# FPGA_board-v1.net
KiCad netlist of a schematic drawn in EAGLE
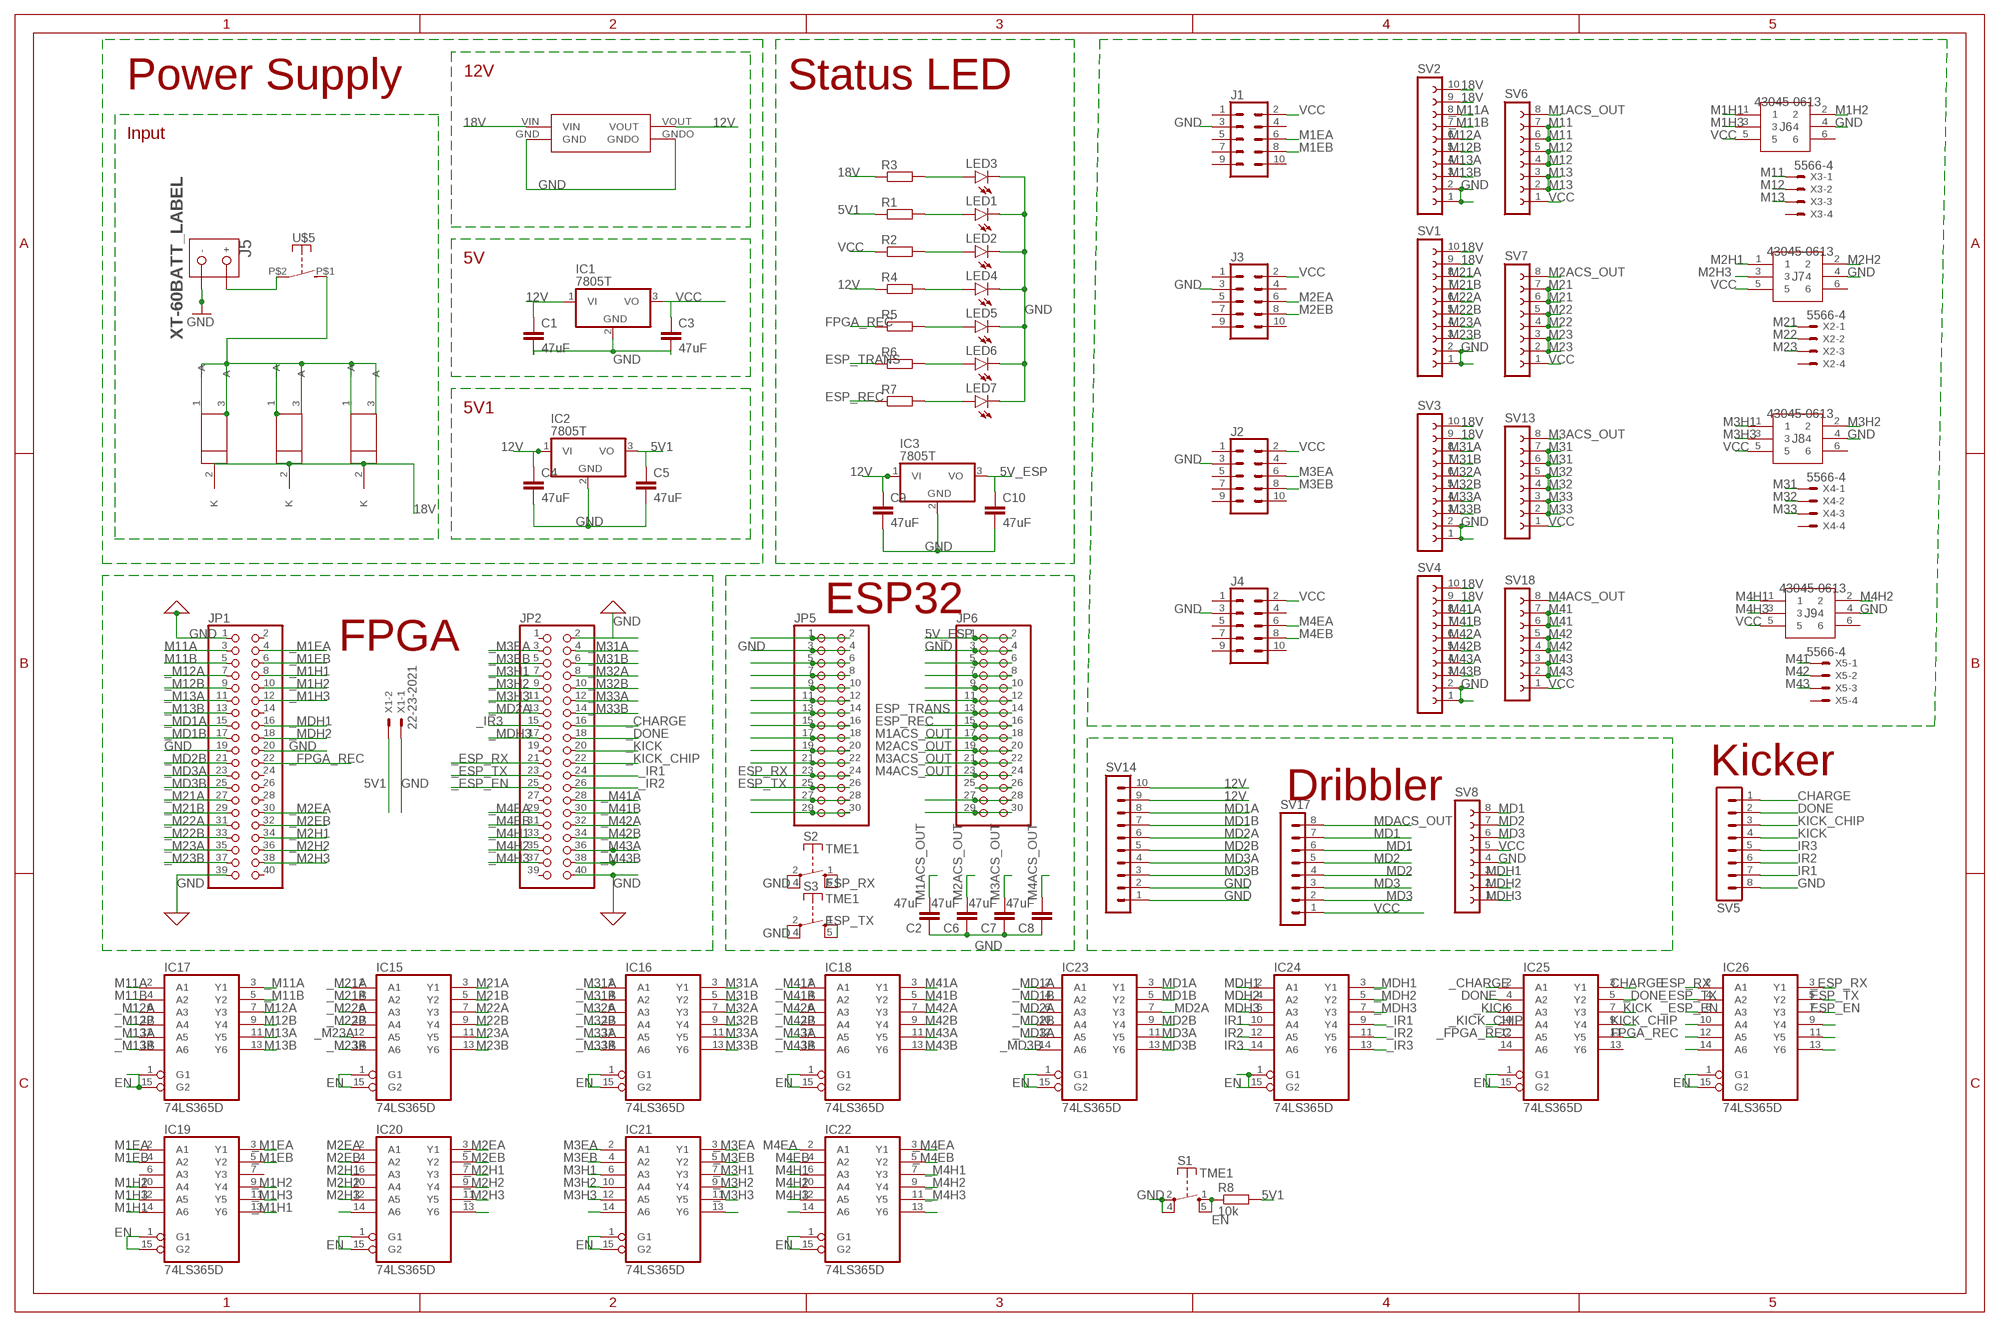
[diagram p0: schematic, sheet 1]

(export (version "E")
  (design (tool "Eeschema 10.0.6"))
  (components
    (comp (ref "C1")
      (value "47uF")
      (footprint "eagle-import:C1206")
      (libsource (lib "eagle-import") (part "C-EUC1206"))
    )
    (comp (ref "C2")
      (value "47uF")
      (footprint "eagle-import:C1206")
      (libsource (lib "eagle-import") (part "C-EUC1206"))
    )
    (comp (ref "C3")
      (value "47uF")
      (footprint "eagle-import:C1206")
      (libsource (lib "eagle-import") (part "C-EUC1206"))
    )
    (comp (ref "C4")
      (value "47uF")
      (footprint "eagle-import:C1206")
      (libsource (lib "eagle-import") (part "C-EUC1206"))
    )
    (comp (ref "C5")
      (value "47uF")
      (footprint "eagle-import:C1206")
      (libsource (lib "eagle-import") (part "C-EUC1206"))
    )
    (comp (ref "C6")
      (value "47uF")
      (footprint "eagle-import:C1206")
      (libsource (lib "eagle-import") (part "C-EUC1206"))
    )
    (comp (ref "C7")
      (value "47uF")
      (footprint "eagle-import:C1206")
      (libsource (lib "eagle-import") (part "C-EUC1206"))
    )
    (comp (ref "C8")
      (value "47uF")
      (footprint "eagle-import:C1206")
      (libsource (lib "eagle-import") (part "C-EUC1206"))
    )
    (comp (ref "C9")
      (value "47uF")
      (footprint "eagle-import:C1206")
      (libsource (lib "eagle-import") (part "C-EUC1206"))
    )
    (comp (ref "C10")
      (value "47uF")
      (footprint "eagle-import:C1206")
      (libsource (lib "eagle-import") (part "C-EUC1206"))
    )
    (comp (ref "IC1")
      (value "7805T")
      (footprint "eagle-import:TO220H")
      (libsource (lib "eagle-import") (part "78T05"))
    )
    (comp (ref "IC2")
      (value "7805T")
      (footprint "eagle-import:TO220H")
      (libsource (lib "eagle-import") (part "78T05"))
    )
    (comp (ref "IC3")
      (value "7805T")
      (footprint "eagle-import:TO220H")
      (libsource (lib "eagle-import") (part "78T05"))
    )
    (comp (ref "IC15")
      (value "74LS365D")
      (footprint "eagle-import:SO16")
      (libsource (lib "eagle-import") (part "74365DLS"))
    )
    (comp (ref "IC16")
      (value "74LS365D")
      (footprint "eagle-import:SO16")
      (libsource (lib "eagle-import") (part "74365DLS"))
    )
    (comp (ref "IC17")
      (value "74LS365D")
      (footprint "eagle-import:SO16")
      (libsource (lib "eagle-import") (part "74365DLS"))
    )
    (comp (ref "IC18")
      (value "74LS365D")
      (footprint "eagle-import:SO16")
      (libsource (lib "eagle-import") (part "74365DLS"))
    )
    (comp (ref "IC19")
      (value "74LS365D")
      (footprint "eagle-import:SO16")
      (libsource (lib "eagle-import") (part "74365DLS"))
    )
    (comp (ref "IC20")
      (value "74LS365D")
      (footprint "eagle-import:SO16")
      (libsource (lib "eagle-import") (part "74365DLS"))
    )
    (comp (ref "IC21")
      (value "74LS365D")
      (footprint "eagle-import:SO16")
      (libsource (lib "eagle-import") (part "74365DLS"))
    )
    (comp (ref "IC22")
      (value "74LS365D")
      (footprint "eagle-import:SO16")
      (libsource (lib "eagle-import") (part "74365DLS"))
    )
    (comp (ref "IC23")
      (value "74LS365D")
      (footprint "eagle-import:SO16")
      (libsource (lib "eagle-import") (part "74365DLS"))
    )
    (comp (ref "IC24")
      (value "74LS365D")
      (footprint "eagle-import:SO16")
      (libsource (lib "eagle-import") (part "74365DLS"))
    )
    (comp (ref "IC25")
      (value "74LS365D")
      (footprint "eagle-import:SO16")
      (libsource (lib "eagle-import") (part "74365DLS"))
    )
    (comp (ref "IC26")
      (value "74LS365D")
      (footprint "eagle-import:SO16")
      (libsource (lib "eagle-import") (part "74365DLS"))
    )
    (comp (ref "J1")
      (value "CONN_05X2SHD_LOCK")
      (footprint "eagle-import:2X5-SHROUDED_LOCK")
      (libsource (lib "eagle-import") (part "CONN_05X2SHD_LOCK"))
    )
    (comp (ref "J2")
      (value "CONN_05X2SHD_LOCK")
      (footprint "eagle-import:2X5-SHROUDED_LOCK")
      (libsource (lib "eagle-import") (part "CONN_05X2SHD_LOCK"))
    )
    (comp (ref "J3")
      (value "CONN_05X2SHD_LOCK")
      (footprint "eagle-import:2X5-SHROUDED_LOCK")
      (libsource (lib "eagle-import") (part "CONN_05X2SHD_LOCK"))
    )
    (comp (ref "J4")
      (value "CONN_05X2SHD_LOCK")
      (footprint "eagle-import:2X5-SHROUDED_LOCK")
      (libsource (lib "eagle-import") (part "CONN_05X2SHD_LOCK"))
    )
    (comp (ref "J5")
      (value "XT-60BATT_LABEL")
      (footprint "eagle-import:XT-60")
      (libsource (lib "eagle-import") (part "XT-60BATT_LABEL"))
    )
    (comp (ref "J6")
      (value "43045-0613")
      (footprint "eagle-import:43045-0613")
      (fields (field (name "MOUSER_PART_NUMBER") "538-43045-0613") (field (name "RS_PART_NUMBER") "6700377P"))
      (libsource (lib "eagle-import") (part "43045-0613"))
    )
    (comp (ref "J7")
      (value "43045-0613")
      (footprint "eagle-import:43045-0613")
      (fields (field (name "MOUSER_PART_NUMBER") "538-43045-0613") (field (name "RS_PART_NUMBER") "6700377P"))
      (libsource (lib "eagle-import") (part "43045-0613"))
    )
    (comp (ref "J8")
      (value "43045-0613")
      (footprint "eagle-import:43045-0613")
      (fields (field (name "MOUSER_PART_NUMBER") "538-43045-0613") (field (name "RS_PART_NUMBER") "6700377P"))
      (libsource (lib "eagle-import") (part "43045-0613"))
    )
    (comp (ref "J9")
      (value "43045-0613")
      (footprint "eagle-import:43045-0613")
      (fields (field (name "MOUSER_PART_NUMBER") "538-43045-0613") (field (name "RS_PART_NUMBER") "6700377P"))
      (libsource (lib "eagle-import") (part "43045-0613"))
    )
    (comp (ref "JP1")
      (value "PINHD-2X20")
      (footprint "eagle-import:2X20")
      (libsource (lib "eagle-import") (part "PINHD-2X20"))
    )
    (comp (ref "JP2")
      (value "PINHD-2X20")
      (footprint "eagle-import:2X20")
      (libsource (lib "eagle-import") (part "PINHD-2X20"))
    )
    (comp (ref "JP5")
      (value "PINHD-2X15")
      (footprint "eagle-import:2X15")
      (libsource (lib "eagle-import") (part "PINHD-2X15"))
    )
    (comp (ref "JP6")
      (value "PINHD-2X15")
      (footprint "eagle-import:2X15")
      (libsource (lib "eagle-import") (part "PINHD-2X15"))
    )
    (comp (ref "LED1")
      (value "LEDSMT1206")
      (footprint "eagle-import:1206")
      (libsource (lib "eagle-import") (part "LEDSMT1206"))
    )
    (comp (ref "LED2")
      (value "LEDSMT1206")
      (footprint "eagle-import:1206")
      (libsource (lib "eagle-import") (part "LEDSMT1206"))
    )
    (comp (ref "LED3")
      (value "LEDSMT1206")
      (footprint "eagle-import:1206")
      (libsource (lib "eagle-import") (part "LEDSMT1206"))
    )
    (comp (ref "LED4")
      (value "LEDSMT1206")
      (footprint "eagle-import:1206")
      (libsource (lib "eagle-import") (part "LEDSMT1206"))
    )
    (comp (ref "LED5")
      (value "LEDSMT1206")
      (footprint "eagle-import:1206")
      (libsource (lib "eagle-import") (part "LEDSMT1206"))
    )
    (comp (ref "LED6")
      (value "LEDSMT1206")
      (footprint "eagle-import:1206")
      (libsource (lib "eagle-import") (part "LEDSMT1206"))
    )
    (comp (ref "LED7")
      (value "LEDSMT1206")
      (footprint "eagle-import:1206")
      (libsource (lib "eagle-import") (part "LEDSMT1206"))
    )
    (comp (ref "R1")
      (value "R-EU_R1206")
      (footprint "eagle-import:R1206")
      (libsource (lib "eagle-import") (part "R-EU_R1206"))
    )
    (comp (ref "R2")
      (value "R-EU_R1206")
      (footprint "eagle-import:R1206")
      (libsource (lib "eagle-import") (part "R-EU_R1206"))
    )
    (comp (ref "R3")
      (value "R-EU_R1206")
      (footprint "eagle-import:R1206")
      (libsource (lib "eagle-import") (part "R-EU_R1206"))
    )
    (comp (ref "R4")
      (value "R-EU_R1206")
      (footprint "eagle-import:R1206")
      (libsource (lib "eagle-import") (part "R-EU_R1206"))
    )
    (comp (ref "R5")
      (value "R-EU_R1206")
      (footprint "eagle-import:R1206")
      (libsource (lib "eagle-import") (part "R-EU_R1206"))
    )
    (comp (ref "R6")
      (value "R-EU_R1206")
      (footprint "eagle-import:R1206")
      (libsource (lib "eagle-import") (part "R-EU_R1206"))
    )
    (comp (ref "R7")
      (value "R-EU_R1206")
      (footprint "eagle-import:R1206")
      (libsource (lib "eagle-import") (part "R-EU_R1206"))
    )
    (comp (ref "R8")
      (value "10k")
      (footprint "eagle-import:0204_7")
      (libsource (lib "eagle-import") (part "R-EU_0204/7"))
    )
    (comp (ref "S1")
      (value "TME1")
      (footprint "eagle-import:TME1")
      (libsource (lib "eagle-import") (part "TME1"))
    )
    (comp (ref "S2")
      (value "TME1")
      (footprint "eagle-import:TME1")
      (libsource (lib "eagle-import") (part "TME1"))
    )
    (comp (ref "S3")
      (value "TME1")
      (footprint "eagle-import:TME1")
      (libsource (lib "eagle-import") (part "TME1"))
    )
    (comp (ref "SV1")
      (value "FE10-1")
      (footprint "eagle-import:FE10")
      (libsource (lib "eagle-import") (part "FE10-1"))
    )
    (comp (ref "SV2")
      (value "FE10-1")
      (footprint "eagle-import:FE10")
      (libsource (lib "eagle-import") (part "FE10-1"))
    )
    (comp (ref "SV3")
      (value "FE10-1")
      (footprint "eagle-import:FE10")
      (libsource (lib "eagle-import") (part "FE10-1"))
    )
    (comp (ref "SV4")
      (value "FE10-1")
      (footprint "eagle-import:FE10")
      (libsource (lib "eagle-import") (part "FE10-1"))
    )
    (comp (ref "SV5")
      (value "MA08-1")
      (footprint "eagle-import:MA08-1")
      (libsource (lib "eagle-import") (part "MA08-1"))
    )
    (comp (ref "SV6")
      (value "FE08-1")
      (footprint "eagle-import:FE08")
      (libsource (lib "eagle-import") (part "FE08-1"))
    )
    (comp (ref "SV7")
      (value "FE08-1")
      (footprint "eagle-import:FE08")
      (libsource (lib "eagle-import") (part "FE08-1"))
    )
    (comp (ref "SV8")
      (value "FE08-1")
      (footprint "eagle-import:FE08")
      (libsource (lib "eagle-import") (part "FE08-1"))
    )
    (comp (ref "SV13")
      (value "FE08-1")
      (footprint "eagle-import:FE08")
      (libsource (lib "eagle-import") (part "FE08-1"))
    )
    (comp (ref "SV14")
      (value "MA10-1")
      (footprint "eagle-import:MA10-1")
      (libsource (lib "eagle-import") (part "MA10-1"))
    )
    (comp (ref "SV17")
      (value "MA08-1")
      (footprint "eagle-import:MA08-1")
      (libsource (lib "eagle-import") (part "MA08-1"))
    )
    (comp (ref "SV18")
      (value "FE08-1")
      (footprint "eagle-import:FE08")
      (libsource (lib "eagle-import") (part "FE08-1"))
    )
    (comp (ref "U$4")
      (value "BUCK")
      (footprint "eagle-import:BUCK")
      (libsource (lib "eagle-import") (part "BUCK"))
    )
    (comp (ref "U$5")
      (value "SWITCH_DA10")
      (footprint "eagle-import:DA10")
      (libsource (lib "eagle-import") (part "SWITCH_DA10"))
    )
    (comp (ref "U1")
      (value "LP38690DT-3.3")
      (footprint "eagle-import:TO228P1042X238-3N")
      (libsource (lib "eagle-import") (part "LP38690DT-3.3"))
    )
    (comp (ref "U2")
      (value "LP38690DT-3.3")
      (footprint "eagle-import:TO228P1042X238-3N")
      (libsource (lib "eagle-import") (part "LP38690DT-3.3"))
    )
    (comp (ref "U3")
      (value "LP38690DT-3.3")
      (footprint "eagle-import:TO228P1042X238-3N")
      (libsource (lib "eagle-import") (part "LP38690DT-3.3"))
    )
    (comp (ref "X1")
      (value "22-23-2021")
      (footprint "eagle-import:22-23-2021")
      (fields (field (name "MF") "MOLEX"))
      (libsource (lib "eagle-import") (part "22-23-2021"))
    )
    (comp (ref "X2")
      (value "5566-4")
      (footprint "eagle-import:5566-4")
      (fields (field (name "MF") "MOLEX"))
      (libsource (lib "eagle-import") (part "5566-4"))
    )
    (comp (ref "X3")
      (value "5566-4")
      (footprint "eagle-import:5566-4")
      (fields (field (name "MF") "MOLEX"))
      (libsource (lib "eagle-import") (part "5566-4"))
    )
    (comp (ref "X4")
      (value "5566-4")
      (footprint "eagle-import:5566-4")
      (fields (field (name "MF") "MOLEX"))
      (libsource (lib "eagle-import") (part "5566-4"))
    )
    (comp (ref "X5")
      (value "5566-4")
      (footprint "eagle-import:5566-4")
      (fields (field (name "MF") "MOLEX"))
      (libsource (lib "eagle-import") (part "5566-4"))
    )
  )
  (nets
    (net (code "1") (name "/5V1") (class "Default")
      (node (ref "C5") (pin "1") (pinfunction "1_1") (pintype "passive"))
      (node (ref "IC2") (pin "3") (pinfunction "VO_3") (pintype "passive"))
      (node (ref "R1") (pin "1") (pinfunction "1_1") (pintype "passive"))
      (node (ref "R8") (pin "2") (pinfunction "2_2") (pintype "passive"))
      (node (ref "X1") (pin "2") (pinfunction "S_2") (pintype "passive"))
    )
    (net (code "2") (name "/5V_ESP") (class "Default")
      (node (ref "C10") (pin "1") (pinfunction "1_1") (pintype "passive"))
      (node (ref "IC3") (pin "3") (pinfunction "VO_3") (pintype "passive"))
      (node (ref "JP6") (pin "1") (pinfunction "1_1") (pintype "passive"))
      (node (ref "JP6") (pin "2") (pinfunction "2_2") (pintype "passive"))
    )
    (net (code "3") (name "/12V") (class "Default")
      (node (ref "C1") (pin "1") (pinfunction "1_1") (pintype "passive"))
      (node (ref "C4") (pin "1") (pinfunction "1_1") (pintype "passive"))
      (node (ref "C9") (pin "1") (pinfunction "1_1") (pintype "passive"))
      (node (ref "IC1") (pin "1") (pinfunction "VI_1") (pintype "input"))
      (node (ref "IC2") (pin "1") (pinfunction "VI_1") (pintype "input"))
      (node (ref "IC3") (pin "1") (pinfunction "VI_1") (pintype "input"))
      (node (ref "R4") (pin "1") (pinfunction "1_1") (pintype "passive"))
      (node (ref "SV14") (pin "10") (pinfunction "10_10") (pintype "passive"))
      (node (ref "SV14") (pin "9") (pinfunction "9_9") (pintype "passive"))
      (node (ref "U$4") (pin "VOUT") (pinfunction "VOUT_VOUT") (pintype "bidirectional"))
    )
    (net (code "4") (name "/18V") (class "Default")
      (node (ref "R3") (pin "1") (pinfunction "1_1") (pintype "passive"))
      (node (ref "SV1") (pin "10") (pinfunction "10_10") (pintype "passive"))
      (node (ref "SV1") (pin "9") (pinfunction "9_9") (pintype "passive"))
      (node (ref "SV2") (pin "10") (pinfunction "10_10") (pintype "passive"))
      (node (ref "SV2") (pin "9") (pinfunction "9_9") (pintype "passive"))
      (node (ref "SV3") (pin "10") (pinfunction "10_10") (pintype "passive"))
      (node (ref "SV3") (pin "9") (pinfunction "9_9") (pintype "passive"))
      (node (ref "SV4") (pin "10") (pinfunction "10_10") (pintype "passive"))
      (node (ref "SV4") (pin "9") (pinfunction "9_9") (pintype "passive"))
      (node (ref "U$4") (pin "VIN") (pinfunction "VIN_VIN") (pintype "bidirectional"))
      (node (ref "U1") (pin "2") (pinfunction "K_2") (pintype "bidirectional"))
      (node (ref "U2") (pin "2") (pinfunction "K_2") (pintype "bidirectional"))
      (node (ref "U3") (pin "2") (pinfunction "K_2") (pintype "bidirectional"))
    )
    (net (code "5") (name "/CHARGE") (class "Default")
      (node (ref "IC25") (pin "3") (pinfunction "Y1_3") (pintype "tri_state"))
      (node (ref "SV5") (pin "1") (pinfunction "1_1") (pintype "passive"))
    )
    (net (code "6") (name "/DONE") (class "Default")
      (node (ref "IC25") (pin "4") (pinfunction "A2_4") (pintype "input"))
      (node (ref "SV5") (pin "2") (pinfunction "2_2") (pintype "passive"))
    )
    (net (code "7") (name "/EN") (class "Default")
      (node (ref "IC15") (pin "1") (pinfunction "G1_1") (pintype "input"))
      (node (ref "IC15") (pin "15") (pinfunction "G2_15") (pintype "input"))
      (node (ref "IC16") (pin "1") (pinfunction "G1_1") (pintype "input"))
      (node (ref "IC16") (pin "15") (pinfunction "G2_15") (pintype "input"))
      (node (ref "IC17") (pin "1") (pinfunction "G1_1") (pintype "input"))
      (node (ref "IC17") (pin "15") (pinfunction "G2_15") (pintype "input"))
      (node (ref "IC18") (pin "1") (pinfunction "G1_1") (pintype "input"))
      (node (ref "IC18") (pin "15") (pinfunction "G2_15") (pintype "input"))
      (node (ref "IC19") (pin "1") (pinfunction "G1_1") (pintype "input"))
      (node (ref "IC19") (pin "15") (pinfunction "G2_15") (pintype "input"))
      (node (ref "IC20") (pin "1") (pinfunction "G1_1") (pintype "input"))
      (node (ref "IC20") (pin "15") (pinfunction "G2_15") (pintype "input"))
      (node (ref "IC21") (pin "1") (pinfunction "G1_1") (pintype "input"))
      (node (ref "IC21") (pin "15") (pinfunction "G2_15") (pintype "input"))
      (node (ref "IC22") (pin "1") (pinfunction "G1_1") (pintype "input"))
      (node (ref "IC22") (pin "15") (pinfunction "G2_15") (pintype "input"))
      (node (ref "IC23") (pin "1") (pinfunction "G1_1") (pintype "input"))
      (node (ref "IC23") (pin "15") (pinfunction "G2_15") (pintype "input"))
      (node (ref "IC24") (pin "1") (pinfunction "G1_1") (pintype "input"))
      (node (ref "IC24") (pin "15") (pinfunction "G2_15") (pintype "input"))
      (node (ref "IC25") (pin "1") (pinfunction "G1_1") (pintype "input"))
      (node (ref "IC25") (pin "15") (pinfunction "G2_15") (pintype "input"))
      (node (ref "IC26") (pin "1") (pinfunction "G1_1") (pintype "input"))
      (node (ref "IC26") (pin "15") (pinfunction "G2_15") (pintype "input"))
      (node (ref "R8") (pin "1") (pinfunction "1_1") (pintype "passive"))
      (node (ref "S1") (pin "1") (pinfunction "S_1") (pintype "passive"))
      (node (ref "S1") (pin "5") (pinfunction "S_5") (pintype "passive"))
    )
    (net (code "8") (name "/ESP_EN") (class "Default")
      (node (ref "IC26") (pin "7") (pinfunction "Y3_7") (pintype "tri_state"))
    )
    (net (code "9") (name "/ESP_REC") (class "Default")
      (node (ref "JP6") (pin "15") (pinfunction "15_15") (pintype "passive"))
      (node (ref "JP6") (pin "16") (pinfunction "16_16") (pintype "passive"))
      (node (ref "R7") (pin "1") (pinfunction "1_1") (pintype "passive"))
    )
    (net (code "10") (name "/ESP_RX") (class "Default")
      (node (ref "IC26") (pin "2") (pinfunction "A1_2") (pintype "input"))
      (node (ref "JP5") (pin "23") (pinfunction "23_23") (pintype "passive"))
      (node (ref "JP5") (pin "24") (pinfunction "24_24") (pintype "passive"))
      (node (ref "S2") (pin "1") (pinfunction "S_1") (pintype "passive"))
      (node (ref "S2") (pin "5") (pinfunction "S_5") (pintype "passive"))
    )
    (net (code "11") (name "/ESP_TRANS") (class "Default")
      (node (ref "JP6") (pin "13") (pinfunction "13_13") (pintype "passive"))
      (node (ref "JP6") (pin "14") (pinfunction "14_14") (pintype "passive"))
      (node (ref "R6") (pin "1") (pinfunction "1_1") (pintype "passive"))
    )
    (net (code "12") (name "/ESP_TX") (class "Default")
      (node (ref "IC26") (pin "5") (pinfunction "Y2_5") (pintype "tri_state"))
      (node (ref "JP5") (pin "25") (pinfunction "25_25") (pintype "passive"))
      (node (ref "JP5") (pin "26") (pinfunction "26_26") (pintype "passive"))
      (node (ref "S3") (pin "1") (pinfunction "S_1") (pintype "passive"))
      (node (ref "S3") (pin "5") (pinfunction "S_5") (pintype "passive"))
    )
    (net (code "13") (name "/FPGA_REC") (class "Default")
      (node (ref "IC25") (pin "11") (pinfunction "Y5_11") (pintype "tri_state"))
      (node (ref "R5") (pin "1") (pinfunction "1_1") (pintype "passive"))
    )
    (net (code "14") (name "/IR1") (class "Default")
      (node (ref "IC24") (pin "10") (pinfunction "A4_10") (pintype "input"))
      (node (ref "SV5") (pin "7") (pinfunction "7_7") (pintype "passive"))
    )
    (net (code "15") (name "/IR2") (class "Default")
      (node (ref "IC24") (pin "12") (pinfunction "A5_12") (pintype "input"))
      (node (ref "SV5") (pin "6") (pinfunction "6_6") (pintype "passive"))
    )
    (net (code "16") (name "/IR3") (class "Default")
      (node (ref "IC24") (pin "14") (pinfunction "A6_14") (pintype "input"))
      (node (ref "SV5") (pin "5") (pinfunction "5_5") (pintype "passive"))
    )
    (net (code "17") (name "/KICK") (class "Default")
      (node (ref "IC25") (pin "7") (pinfunction "Y3_7") (pintype "tri_state"))
      (node (ref "SV5") (pin "4") (pinfunction "4_4") (pintype "passive"))
    )
    (net (code "18") (name "/KICK_CHIP") (class "Default")
      (node (ref "IC25") (pin "9") (pinfunction "Y4_9") (pintype "tri_state"))
      (node (ref "SV5") (pin "3") (pinfunction "3_3") (pintype "passive"))
    )
    (net (code "19") (name "/M1ACS_OUT") (class "Default")
      (node (ref "C2") (pin "2") (pinfunction "2_2") (pintype "passive"))
      (node (ref "JP6") (pin "17") (pinfunction "17_17") (pintype "passive"))
      (node (ref "JP6") (pin "18") (pinfunction "18_18") (pintype "passive"))
      (node (ref "SV6") (pin "8") (pinfunction "8_8") (pintype "passive"))
    )
    (net (code "20") (name "/M1EA") (class "Default")
      (node (ref "IC19") (pin "2") (pinfunction "A1_2") (pintype "input"))
      (node (ref "J1") (pin "6") (pinfunction "6_6") (pintype "passive"))
    )
    (net (code "21") (name "/M1EB") (class "Default")
      (node (ref "IC19") (pin "4") (pinfunction "A2_4") (pintype "input"))
      (node (ref "J1") (pin "8") (pinfunction "8_8") (pintype "passive"))
    )
    (net (code "22") (name "/M1H1") (class "Default")
      (node (ref "IC19") (pin "14") (pinfunction "A6_14") (pintype "input"))
      (node (ref "J6") (pin "1") (pinfunction "1_1") (pintype "bidirectional"))
    )
    (net (code "23") (name "/M1H2") (class "Default")
      (node (ref "IC19") (pin "10") (pinfunction "A4_10") (pintype "input"))
      (node (ref "J6") (pin "2") (pinfunction "2_2") (pintype "bidirectional"))
    )
    (net (code "24") (name "/M1H3") (class "Default")
      (node (ref "IC19") (pin "12") (pinfunction "A5_12") (pintype "input"))
      (node (ref "J6") (pin "3") (pinfunction "3_3") (pintype "bidirectional"))
    )
    (net (code "25") (name "/M2ACS_OUT") (class "Default")
      (node (ref "C6") (pin "2") (pinfunction "2_2") (pintype "passive"))
      (node (ref "JP6") (pin "19") (pinfunction "19_19") (pintype "passive"))
      (node (ref "JP6") (pin "20") (pinfunction "20_20") (pintype "passive"))
      (node (ref "SV7") (pin "8") (pinfunction "8_8") (pintype "passive"))
    )
    (net (code "26") (name "/M2EA") (class "Default")
      (node (ref "IC20") (pin "2") (pinfunction "A1_2") (pintype "input"))
      (node (ref "J3") (pin "6") (pinfunction "6_6") (pintype "passive"))
    )
    (net (code "27") (name "/M2EB") (class "Default")
      (node (ref "IC20") (pin "4") (pinfunction "A2_4") (pintype "input"))
      (node (ref "J3") (pin "8") (pinfunction "8_8") (pintype "passive"))
    )
    (net (code "28") (name "/M2H1") (class "Default")
      (node (ref "IC20") (pin "6") (pinfunction "A3_6") (pintype "input"))
      (node (ref "J7") (pin "1") (pinfunction "1_1") (pintype "bidirectional"))
    )
    (net (code "29") (name "/M2H2") (class "Default")
      (node (ref "IC20") (pin "10") (pinfunction "A4_10") (pintype "input"))
      (node (ref "J7") (pin "2") (pinfunction "2_2") (pintype "bidirectional"))
    )
    (net (code "30") (name "/M2H3") (class "Default")
      (node (ref "IC20") (pin "12") (pinfunction "A5_12") (pintype "input"))
      (node (ref "J7") (pin "3") (pinfunction "3_3") (pintype "bidirectional"))
    )
    (net (code "31") (name "/M3ACS_OUT") (class "Default")
      (node (ref "C7") (pin "2") (pinfunction "2_2") (pintype "passive"))
      (node (ref "JP6") (pin "21") (pinfunction "21_21") (pintype "passive"))
      (node (ref "JP6") (pin "22") (pinfunction "22_22") (pintype "passive"))
      (node (ref "SV13") (pin "8") (pinfunction "8_8") (pintype "passive"))
    )
    (net (code "32") (name "/M3EA") (class "Default")
      (node (ref "IC21") (pin "2") (pinfunction "A1_2") (pintype "input"))
      (node (ref "J2") (pin "6") (pinfunction "6_6") (pintype "passive"))
    )
    (net (code "33") (name "/M3EB") (class "Default")
      (node (ref "IC21") (pin "4") (pinfunction "A2_4") (pintype "input"))
      (node (ref "J2") (pin "8") (pinfunction "8_8") (pintype "passive"))
    )
    (net (code "34") (name "/M3H1") (class "Default")
      (node (ref "IC21") (pin "6") (pinfunction "A3_6") (pintype "input"))
      (node (ref "J8") (pin "1") (pinfunction "1_1") (pintype "bidirectional"))
    )
    (net (code "35") (name "/M3H2") (class "Default")
      (node (ref "IC21") (pin "10") (pinfunction "A4_10") (pintype "input"))
      (node (ref "J8") (pin "2") (pinfunction "2_2") (pintype "bidirectional"))
    )
    (net (code "36") (name "/M3H3") (class "Default")
      (node (ref "IC21") (pin "12") (pinfunction "A5_12") (pintype "input"))
      (node (ref "J8") (pin "3") (pinfunction "3_3") (pintype "bidirectional"))
    )
    (net (code "37") (name "/M4ACS_OUT") (class "Default")
      (node (ref "C8") (pin "2") (pinfunction "2_2") (pintype "passive"))
      (node (ref "JP6") (pin "23") (pinfunction "23_23") (pintype "passive"))
      (node (ref "JP6") (pin "24") (pinfunction "24_24") (pintype "passive"))
      (node (ref "SV18") (pin "8") (pinfunction "8_8") (pintype "passive"))
    )
    (net (code "38") (name "/M4EA") (class "Default")
      (node (ref "IC22") (pin "2") (pinfunction "A1_2") (pintype "input"))
      (node (ref "J4") (pin "6") (pinfunction "6_6") (pintype "passive"))
    )
    (net (code "39") (name "/M4EB") (class "Default")
      (node (ref "IC22") (pin "4") (pinfunction "A2_4") (pintype "input"))
      (node (ref "J4") (pin "8") (pinfunction "8_8") (pintype "passive"))
    )
    (net (code "40") (name "/M4H1") (class "Default")
      (node (ref "IC22") (pin "6") (pinfunction "A3_6") (pintype "input"))
      (node (ref "J9") (pin "1") (pinfunction "1_1") (pintype "bidirectional"))
    )
    (net (code "41") (name "/M4H2") (class "Default")
      (node (ref "IC22") (pin "10") (pinfunction "A4_10") (pintype "input"))
      (node (ref "J9") (pin "2") (pinfunction "2_2") (pintype "bidirectional"))
    )
    (net (code "42") (name "/M4H3") (class "Default")
      (node (ref "IC22") (pin "12") (pinfunction "A5_12") (pintype "input"))
      (node (ref "J9") (pin "3") (pinfunction "3_3") (pintype "bidirectional"))
    )
    (net (code "43") (name "/M11") (class "Default")
      (node (ref "SV6") (pin "6") (pinfunction "6_6") (pintype "passive"))
      (node (ref "SV6") (pin "7") (pinfunction "7_7") (pintype "passive"))
      (node (ref "X3") (pin "1") (pinfunction "S_1") (pintype "passive"))
    )
    (net (code "44") (name "/M11A") (class "Default")
      (node (ref "IC17") (pin "2") (pinfunction "A1_2") (pintype "input"))
      (node (ref "JP1") (pin "3") (pinfunction "3_3") (pintype "passive"))
    )
    (net (code "45") (name "/M11B") (class "Default")
      (node (ref "IC17") (pin "4") (pinfunction "A2_4") (pintype "input"))
      (node (ref "JP1") (pin "5") (pinfunction "5_5") (pintype "passive"))
    )
    (net (code "46") (name "/M12") (class "Default")
      (node (ref "SV6") (pin "4") (pinfunction "4_4") (pintype "passive"))
      (node (ref "SV6") (pin "5") (pinfunction "5_5") (pintype "passive"))
      (node (ref "X3") (pin "2") (pinfunction "S_2") (pintype "passive"))
    )
    (net (code "47") (name "/M12A") (class "Default")
      (node (ref "IC17") (pin "7") (pinfunction "Y3_7") (pintype "tri_state"))
      (node (ref "SV2") (pin "6") (pinfunction "6_6") (pintype "passive"))
    )
    (net (code "48") (name "/M12B") (class "Default")
      (node (ref "IC17") (pin "9") (pinfunction "Y4_9") (pintype "tri_state"))
      (node (ref "SV2") (pin "5") (pinfunction "5_5") (pintype "passive"))
    )
    (net (code "49") (name "/M13") (class "Default")
      (node (ref "SV6") (pin "2") (pinfunction "2_2") (pintype "passive"))
      (node (ref "SV6") (pin "3") (pinfunction "3_3") (pintype "passive"))
      (node (ref "X3") (pin "3") (pinfunction "S_3") (pintype "passive"))
    )
    (net (code "50") (name "/M13A") (class "Default")
      (node (ref "IC17") (pin "11") (pinfunction "Y5_11") (pintype "tri_state"))
      (node (ref "SV2") (pin "4") (pinfunction "4_4") (pintype "passive"))
    )
    (net (code "51") (name "/M13B") (class "Default")
      (node (ref "IC17") (pin "13") (pinfunction "Y6_13") (pintype "tri_state"))
      (node (ref "SV2") (pin "3") (pinfunction "3_3") (pintype "passive"))
    )
    (net (code "52") (name "/M21") (class "Default")
      (node (ref "SV7") (pin "6") (pinfunction "6_6") (pintype "passive"))
      (node (ref "SV7") (pin "7") (pinfunction "7_7") (pintype "passive"))
      (node (ref "X2") (pin "1") (pinfunction "S_1") (pintype "passive"))
    )
    (net (code "53") (name "/M21A") (class "Default")
      (node (ref "IC15") (pin "3") (pinfunction "Y1_3") (pintype "tri_state"))
      (node (ref "SV1") (pin "8") (pinfunction "8_8") (pintype "passive"))
    )
    (net (code "54") (name "/M21B") (class "Default")
      (node (ref "IC15") (pin "5") (pinfunction "Y2_5") (pintype "tri_state"))
      (node (ref "SV1") (pin "7") (pinfunction "7_7") (pintype "passive"))
    )
    (net (code "55") (name "/M22") (class "Default")
      (node (ref "SV7") (pin "4") (pinfunction "4_4") (pintype "passive"))
      (node (ref "SV7") (pin "5") (pinfunction "5_5") (pintype "passive"))
      (node (ref "X2") (pin "2") (pinfunction "S_2") (pintype "passive"))
    )
    (net (code "56") (name "/M22A") (class "Default")
      (node (ref "IC15") (pin "7") (pinfunction "Y3_7") (pintype "tri_state"))
      (node (ref "SV1") (pin "6") (pinfunction "6_6") (pintype "passive"))
    )
    (net (code "57") (name "/M22B") (class "Default")
      (node (ref "IC15") (pin "9") (pinfunction "Y4_9") (pintype "tri_state"))
      (node (ref "SV1") (pin "5") (pinfunction "5_5") (pintype "passive"))
    )
    (net (code "58") (name "/M23") (class "Default")
      (node (ref "SV7") (pin "2") (pinfunction "2_2") (pintype "passive"))
      (node (ref "SV7") (pin "3") (pinfunction "3_3") (pintype "passive"))
      (node (ref "X2") (pin "3") (pinfunction "S_3") (pintype "passive"))
    )
    (net (code "59") (name "/M23A") (class "Default")
      (node (ref "IC15") (pin "11") (pinfunction "Y5_11") (pintype "tri_state"))
      (node (ref "SV1") (pin "4") (pinfunction "4_4") (pintype "passive"))
    )
    (net (code "60") (name "/M23B") (class "Default")
      (node (ref "IC15") (pin "13") (pinfunction "Y6_13") (pintype "tri_state"))
      (node (ref "SV1") (pin "3") (pinfunction "3_3") (pintype "passive"))
    )
    (net (code "61") (name "/M31") (class "Default")
      (node (ref "SV13") (pin "6") (pinfunction "6_6") (pintype "passive"))
      (node (ref "SV13") (pin "7") (pinfunction "7_7") (pintype "passive"))
      (node (ref "X4") (pin "1") (pinfunction "S_1") (pintype "passive"))
    )
    (net (code "62") (name "/M31A") (class "Default")
      (node (ref "IC16") (pin "3") (pinfunction "Y1_3") (pintype "tri_state"))
      (node (ref "SV3") (pin "8") (pinfunction "8_8") (pintype "passive"))
    )
    (net (code "63") (name "/M31B") (class "Default")
      (node (ref "IC16") (pin "5") (pinfunction "Y2_5") (pintype "tri_state"))
      (node (ref "SV3") (pin "7") (pinfunction "7_7") (pintype "passive"))
    )
    (net (code "64") (name "/M32") (class "Default")
      (node (ref "SV13") (pin "4") (pinfunction "4_4") (pintype "passive"))
      (node (ref "SV13") (pin "5") (pinfunction "5_5") (pintype "passive"))
      (node (ref "X4") (pin "2") (pinfunction "S_2") (pintype "passive"))
    )
    (net (code "65") (name "/M32A") (class "Default")
      (node (ref "IC16") (pin "7") (pinfunction "Y3_7") (pintype "tri_state"))
      (node (ref "SV3") (pin "6") (pinfunction "6_6") (pintype "passive"))
    )
    (net (code "66") (name "/M32B") (class "Default")
      (node (ref "IC16") (pin "9") (pinfunction "Y4_9") (pintype "tri_state"))
      (node (ref "SV3") (pin "5") (pinfunction "5_5") (pintype "passive"))
    )
    (net (code "67") (name "/M33") (class "Default")
      (node (ref "SV13") (pin "2") (pinfunction "2_2") (pintype "passive"))
      (node (ref "SV13") (pin "3") (pinfunction "3_3") (pintype "passive"))
      (node (ref "X4") (pin "3") (pinfunction "S_3") (pintype "passive"))
    )
    (net (code "68") (name "/M33A") (class "Default")
      (node (ref "IC16") (pin "11") (pinfunction "Y5_11") (pintype "tri_state"))
      (node (ref "SV3") (pin "4") (pinfunction "4_4") (pintype "passive"))
    )
    (net (code "69") (name "/M33B") (class "Default")
      (node (ref "IC16") (pin "13") (pinfunction "Y6_13") (pintype "tri_state"))
      (node (ref "SV3") (pin "3") (pinfunction "3_3") (pintype "passive"))
    )
    (net (code "70") (name "/M41") (class "Default")
      (node (ref "SV18") (pin "6") (pinfunction "6_6") (pintype "passive"))
      (node (ref "SV18") (pin "7") (pinfunction "7_7") (pintype "passive"))
      (node (ref "X5") (pin "1") (pinfunction "S_1") (pintype "passive"))
    )
    (net (code "71") (name "/M41A") (class "Default")
      (node (ref "IC18") (pin "3") (pinfunction "Y1_3") (pintype "tri_state"))
      (node (ref "SV4") (pin "8") (pinfunction "8_8") (pintype "passive"))
    )
    (net (code "72") (name "/M41B") (class "Default")
      (node (ref "IC18") (pin "5") (pinfunction "Y2_5") (pintype "tri_state"))
      (node (ref "SV4") (pin "7") (pinfunction "7_7") (pintype "passive"))
    )
    (net (code "73") (name "/M42") (class "Default")
      (node (ref "SV18") (pin "4") (pinfunction "4_4") (pintype "passive"))
      (node (ref "SV18") (pin "5") (pinfunction "5_5") (pintype "passive"))
      (node (ref "X5") (pin "2") (pinfunction "S_2") (pintype "passive"))
    )
    (net (code "74") (name "/M42A") (class "Default")
      (node (ref "IC18") (pin "7") (pinfunction "Y3_7") (pintype "tri_state"))
      (node (ref "SV4") (pin "6") (pinfunction "6_6") (pintype "passive"))
    )
    (net (code "75") (name "/M42B") (class "Default")
      (node (ref "IC18") (pin "9") (pinfunction "Y4_9") (pintype "tri_state"))
      (node (ref "SV4") (pin "5") (pinfunction "5_5") (pintype "passive"))
    )
    (net (code "76") (name "/M43") (class "Default")
      (node (ref "SV18") (pin "2") (pinfunction "2_2") (pintype "passive"))
      (node (ref "SV18") (pin "3") (pinfunction "3_3") (pintype "passive"))
      (node (ref "X5") (pin "3") (pinfunction "S_3") (pintype "passive"))
    )
    (net (code "77") (name "/M43A") (class "Default")
      (node (ref "IC18") (pin "11") (pinfunction "Y5_11") (pintype "tri_state"))
      (node (ref "SV4") (pin "4") (pinfunction "4_4") (pintype "passive"))
    )
    (net (code "78") (name "/M43B") (class "Default")
      (node (ref "IC18") (pin "13") (pinfunction "Y6_13") (pintype "tri_state"))
      (node (ref "SV4") (pin "3") (pinfunction "3_3") (pintype "passive"))
    )
    (net (code "79") (name "/MD1") (class "Default")
      (node (ref "SV17") (pin "6") (pinfunction "6_6") (pintype "passive"))
      (node (ref "SV17") (pin "7") (pinfunction "7_7") (pintype "passive"))
      (node (ref "SV8") (pin "8") (pinfunction "8_8") (pintype "passive"))
    )
    (net (code "80") (name "/MD1A") (class "Default")
      (node (ref "IC23") (pin "3") (pinfunction "Y1_3") (pintype "tri_state"))
      (node (ref "SV14") (pin "8") (pinfunction "8_8") (pintype "passive"))
    )
    (net (code "81") (name "/MD1B") (class "Default")
      (node (ref "IC23") (pin "5") (pinfunction "Y2_5") (pintype "tri_state"))
      (node (ref "SV14") (pin "7") (pinfunction "7_7") (pintype "passive"))
    )
    (net (code "82") (name "/MD2") (class "Default")
      (node (ref "SV17") (pin "4") (pinfunction "4_4") (pintype "passive"))
      (node (ref "SV17") (pin "5") (pinfunction "5_5") (pintype "passive"))
      (node (ref "SV8") (pin "7") (pinfunction "7_7") (pintype "passive"))
    )
    (net (code "83") (name "/MD2A") (class "Default")
      (node (ref "IC23") (pin "7") (pinfunction "Y3_7") (pintype "tri_state"))
      (node (ref "SV14") (pin "6") (pinfunction "6_6") (pintype "passive"))
    )
    (net (code "84") (name "/MD2B") (class "Default")
      (node (ref "IC23") (pin "9") (pinfunction "Y4_9") (pintype "tri_state"))
      (node (ref "SV14") (pin "5") (pinfunction "5_5") (pintype "passive"))
    )
    (net (code "85") (name "/MD3") (class "Default")
      (node (ref "SV17") (pin "2") (pinfunction "2_2") (pintype "passive"))
      (node (ref "SV17") (pin "3") (pinfunction "3_3") (pintype "passive"))
      (node (ref "SV8") (pin "6") (pinfunction "6_6") (pintype "passive"))
    )
    (net (code "86") (name "/MD3A") (class "Default")
      (node (ref "IC23") (pin "11") (pinfunction "Y5_11") (pintype "tri_state"))
      (node (ref "SV14") (pin "4") (pinfunction "4_4") (pintype "passive"))
    )
    (net (code "87") (name "/MD3B") (class "Default")
      (node (ref "IC23") (pin "13") (pinfunction "Y6_13") (pintype "tri_state"))
      (node (ref "SV14") (pin "3") (pinfunction "3_3") (pintype "passive"))
    )
    (net (code "88") (name "/MDACS_OUT") (class "Default")
      (node (ref "SV17") (pin "8") (pinfunction "8_8") (pintype "passive"))
    )
    (net (code "89") (name "/MDH1") (class "Default")
      (node (ref "IC24") (pin "2") (pinfunction "A1_2") (pintype "input"))
      (node (ref "SV8") (pin "3") (pinfunction "3_3") (pintype "passive"))
    )
    (net (code "90") (name "/MDH2") (class "Default")
      (node (ref "IC24") (pin "4") (pinfunction "A2_4") (pintype "input"))
      (node (ref "SV8") (pin "2") (pinfunction "2_2") (pintype "passive"))
    )
    (net (code "91") (name "/MDH3") (class "Default")
      (node (ref "IC24") (pin "6") (pinfunction "A3_6") (pintype "input"))
      (node (ref "SV8") (pin "1") (pinfunction "1_1") (pintype "passive"))
    )
    (net (code "92") (name "/VCC") (class "Default")
      (node (ref "C3") (pin "1") (pinfunction "1_1") (pintype "passive"))
      (node (ref "IC1") (pin "3") (pinfunction "VO_3") (pintype "passive"))
      (node (ref "J1") (pin "2") (pinfunction "2_2") (pintype "passive"))
      (node (ref "J2") (pin "2") (pinfunction "2_2") (pintype "passive"))
      (node (ref "J3") (pin "2") (pinfunction "2_2") (pintype "passive"))
      (node (ref "J4") (pin "2") (pinfunction "2_2") (pintype "passive"))
      (node (ref "J6") (pin "5") (pinfunction "5_5") (pintype "bidirectional"))
      (node (ref "J7") (pin "5") (pinfunction "5_5") (pintype "bidirectional"))
      (node (ref "J8") (pin "5") (pinfunction "5_5") (pintype "bidirectional"))
      (node (ref "J9") (pin "5") (pinfunction "5_5") (pintype "bidirectional"))
      (node (ref "R2") (pin "1") (pinfunction "1_1") (pintype "passive"))
      (node (ref "SV13") (pin "1") (pinfunction "1_1") (pintype "passive"))
      (node (ref "SV17") (pin "1") (pinfunction "1_1") (pintype "passive"))
      (node (ref "SV18") (pin "1") (pinfunction "1_1") (pintype "passive"))
      (node (ref "SV6") (pin "1") (pinfunction "1_1") (pintype "passive"))
      (node (ref "SV7") (pin "1") (pinfunction "1_1") (pintype "passive"))
      (node (ref "SV8") (pin "5") (pinfunction "5_5") (pintype "passive"))
    )
    (net (code "93") (name "/_CHARGE") (class "Default")
      (node (ref "IC25") (pin "2") (pinfunction "A1_2") (pintype "input"))
      (node (ref "JP2") (pin "16") (pinfunction "16_16") (pintype "passive"))
    )
    (net (code "94") (name "/_DONE") (class "Default")
      (node (ref "IC25") (pin "5") (pinfunction "Y2_5") (pintype "tri_state"))
      (node (ref "JP2") (pin "18") (pinfunction "18_18") (pintype "passive"))
    )
    (net (code "95") (name "/_ESP_EN") (class "Default")
      (node (ref "IC26") (pin "6") (pinfunction "A3_6") (pintype "input"))
      (node (ref "JP2") (pin "25") (pinfunction "25_25") (pintype "passive"))
    )
    (net (code "96") (name "/_ESP_RX") (class "Default")
      (node (ref "IC26") (pin "3") (pinfunction "Y1_3") (pintype "tri_state"))
      (node (ref "JP2") (pin "21") (pinfunction "21_21") (pintype "passive"))
    )
    (net (code "97") (name "/_ESP_TX") (class "Default")
      (node (ref "IC26") (pin "4") (pinfunction "A2_4") (pintype "input"))
      (node (ref "JP2") (pin "23") (pinfunction "23_23") (pintype "passive"))
    )
    (net (code "98") (name "/_FPGA_REC") (class "Default")
      (node (ref "IC25") (pin "12") (pinfunction "A5_12") (pintype "input"))
      (node (ref "JP1") (pin "22") (pinfunction "22_22") (pintype "passive"))
    )
    (net (code "99") (name "/_IR1") (class "Default")
      (node (ref "IC24") (pin "9") (pinfunction "Y4_9") (pintype "tri_state"))
      (node (ref "JP2") (pin "24") (pinfunction "24_24") (pintype "passive"))
    )
    (net (code "100") (name "/_IR2") (class "Default")
      (node (ref "IC24") (pin "11") (pinfunction "Y5_11") (pintype "tri_state"))
      (node (ref "JP2") (pin "26") (pinfunction "26_26") (pintype "passive"))
    )
    (net (code "101") (name "/_IR3") (class "Default")
      (node (ref "IC24") (pin "13") (pinfunction "Y6_13") (pintype "tri_state"))
      (node (ref "JP2") (pin "15") (pinfunction "15_15") (pintype "passive"))
    )
    (net (code "102") (name "/_KICK") (class "Default")
      (node (ref "IC25") (pin "6") (pinfunction "A3_6") (pintype "input"))
      (node (ref "JP2") (pin "20") (pinfunction "20_20") (pintype "passive"))
    )
    (net (code "103") (name "/_KICK_CHIP") (class "Default")
      (node (ref "IC25") (pin "10") (pinfunction "A4_10") (pintype "input"))
      (node (ref "JP2") (pin "22") (pinfunction "22_22") (pintype "passive"))
    )
    (net (code "104") (name "/_M1EA") (class "Default")
      (node (ref "IC19") (pin "3") (pinfunction "Y1_3") (pintype "tri_state"))
      (node (ref "JP1") (pin "4") (pinfunction "4_4") (pintype "passive"))
    )
    (net (code "105") (name "/_M1EB") (class "Default")
      (node (ref "IC19") (pin "5") (pinfunction "Y2_5") (pintype "tri_state"))
      (node (ref "JP1") (pin "6") (pinfunction "6_6") (pintype "passive"))
    )
    (net (code "106") (name "/_M1H1") (class "Default")
      (node (ref "IC19") (pin "13") (pinfunction "Y6_13") (pintype "tri_state"))
      (node (ref "JP1") (pin "8") (pinfunction "8_8") (pintype "passive"))
    )
    (net (code "107") (name "/_M1H2") (class "Default")
      (node (ref "IC19") (pin "9") (pinfunction "Y4_9") (pintype "tri_state"))
      (node (ref "JP1") (pin "10") (pinfunction "10_10") (pintype "passive"))
    )
    (net (code "108") (name "/_M1H3") (class "Default")
      (node (ref "IC19") (pin "11") (pinfunction "Y5_11") (pintype "tri_state"))
      (node (ref "JP1") (pin "12") (pinfunction "12_12") (pintype "passive"))
    )
    (net (code "109") (name "/_M2EA") (class "Default")
      (node (ref "IC20") (pin "3") (pinfunction "Y1_3") (pintype "tri_state"))
      (node (ref "JP1") (pin "30") (pinfunction "30_30") (pintype "passive"))
    )
    (net (code "110") (name "/_M2EB") (class "Default")
      (node (ref "IC20") (pin "5") (pinfunction "Y2_5") (pintype "tri_state"))
      (node (ref "JP1") (pin "32") (pinfunction "32_32") (pintype "passive"))
    )
    (net (code "111") (name "/_M2H1") (class "Default")
      (node (ref "IC20") (pin "7") (pinfunction "Y3_7") (pintype "tri_state"))
      (node (ref "JP1") (pin "34") (pinfunction "34_34") (pintype "passive"))
    )
    (net (code "112") (name "/_M2H2") (class "Default")
      (node (ref "IC20") (pin "9") (pinfunction "Y4_9") (pintype "tri_state"))
      (node (ref "JP1") (pin "36") (pinfunction "36_36") (pintype "passive"))
    )
    (net (code "113") (name "/_M2H3") (class "Default")
      (node (ref "IC20") (pin "11") (pinfunction "Y5_11") (pintype "tri_state"))
      (node (ref "JP1") (pin "38") (pinfunction "38_38") (pintype "passive"))
    )
    (net (code "114") (name "/_M3EA") (class "Default")
      (node (ref "IC21") (pin "3") (pinfunction "Y1_3") (pintype "tri_state"))
      (node (ref "JP2") (pin "3") (pinfunction "3_3") (pintype "passive"))
    )
    (net (code "115") (name "/_M3EB") (class "Default")
      (node (ref "IC21") (pin "5") (pinfunction "Y2_5") (pintype "tri_state"))
      (node (ref "JP2") (pin "5") (pinfunction "5_5") (pintype "passive"))
    )
    (net (code "116") (name "/_M3H1") (class "Default")
      (node (ref "IC21") (pin "7") (pinfunction "Y3_7") (pintype "tri_state"))
      (node (ref "JP2") (pin "7") (pinfunction "7_7") (pintype "passive"))
    )
    (net (code "117") (name "/_M3H2") (class "Default")
      (node (ref "IC21") (pin "9") (pinfunction "Y4_9") (pintype "tri_state"))
      (node (ref "JP2") (pin "9") (pinfunction "9_9") (pintype "passive"))
    )
    (net (code "118") (name "/_M3H3") (class "Default")
      (node (ref "IC21") (pin "11") (pinfunction "Y5_11") (pintype "tri_state"))
      (node (ref "JP2") (pin "11") (pinfunction "11_11") (pintype "passive"))
    )
    (net (code "119") (name "/_M4EA") (class "Default")
      (node (ref "IC22") (pin "3") (pinfunction "Y1_3") (pintype "tri_state"))
      (node (ref "JP2") (pin "29") (pinfunction "29_29") (pintype "passive"))
    )
    (net (code "120") (name "/_M4EB") (class "Default")
      (node (ref "IC22") (pin "5") (pinfunction "Y2_5") (pintype "tri_state"))
      (node (ref "JP2") (pin "31") (pinfunction "31_31") (pintype "passive"))
    )
    (net (code "121") (name "/_M4H1") (class "Default")
      (node (ref "IC22") (pin "7") (pinfunction "Y3_7") (pintype "tri_state"))
      (node (ref "JP2") (pin "33") (pinfunction "33_33") (pintype "passive"))
    )
    (net (code "122") (name "/_M4H2") (class "Default")
      (node (ref "IC22") (pin "9") (pinfunction "Y4_9") (pintype "tri_state"))
      (node (ref "JP2") (pin "35") (pinfunction "35_35") (pintype "passive"))
    )
    (net (code "123") (name "/_M4H3") (class "Default")
      (node (ref "IC22") (pin "11") (pinfunction "Y5_11") (pintype "tri_state"))
      (node (ref "JP2") (pin "37") (pinfunction "37_37") (pintype "passive"))
    )
    (net (code "124") (name "/_M11A") (class "Default")
      (node (ref "IC17") (pin "3") (pinfunction "Y1_3") (pintype "tri_state"))
      (node (ref "SV2") (pin "8") (pinfunction "8_8") (pintype "passive"))
    )
    (net (code "125") (name "/_M11B") (class "Default")
      (node (ref "IC17") (pin "5") (pinfunction "Y2_5") (pintype "tri_state"))
      (node (ref "SV2") (pin "7") (pinfunction "7_7") (pintype "passive"))
    )
    (net (code "126") (name "/_M12A") (class "Default")
      (node (ref "IC17") (pin "6") (pinfunction "A3_6") (pintype "input"))
      (node (ref "JP1") (pin "7") (pinfunction "7_7") (pintype "passive"))
    )
    (net (code "127") (name "/_M12B") (class "Default")
      (node (ref "IC17") (pin "10") (pinfunction "A4_10") (pintype "input"))
      (node (ref "JP1") (pin "9") (pinfunction "9_9") (pintype "passive"))
    )
    (net (code "128") (name "/_M13A") (class "Default")
      (node (ref "IC17") (pin "12") (pinfunction "A5_12") (pintype "input"))
      (node (ref "JP1") (pin "11") (pinfunction "11_11") (pintype "passive"))
    )
    (net (code "129") (name "/_M13B") (class "Default")
      (node (ref "IC17") (pin "14") (pinfunction "A6_14") (pintype "input"))
      (node (ref "JP1") (pin "13") (pinfunction "13_13") (pintype "passive"))
    )
    (net (code "130") (name "/_M21A") (class "Default")
      (node (ref "IC15") (pin "2") (pinfunction "A1_2") (pintype "input"))
      (node (ref "JP1") (pin "27") (pinfunction "27_27") (pintype "passive"))
    )
    (net (code "131") (name "/_M21B") (class "Default")
      (node (ref "IC15") (pin "4") (pinfunction "A2_4") (pintype "input"))
      (node (ref "JP1") (pin "29") (pinfunction "29_29") (pintype "passive"))
    )
    (net (code "132") (name "/_M22A") (class "Default")
      (node (ref "IC15") (pin "6") (pinfunction "A3_6") (pintype "input"))
      (node (ref "JP1") (pin "31") (pinfunction "31_31") (pintype "passive"))
    )
    (net (code "133") (name "/_M22B") (class "Default")
      (node (ref "IC15") (pin "10") (pinfunction "A4_10") (pintype "input"))
      (node (ref "JP1") (pin "33") (pinfunction "33_33") (pintype "passive"))
    )
    (net (code "134") (name "/_M23A") (class "Default")
      (node (ref "IC15") (pin "12") (pinfunction "A5_12") (pintype "input"))
      (node (ref "JP1") (pin "35") (pinfunction "35_35") (pintype "passive"))
    )
    (net (code "135") (name "/_M23B") (class "Default")
      (node (ref "IC15") (pin "14") (pinfunction "A6_14") (pintype "input"))
      (node (ref "JP1") (pin "37") (pinfunction "37_37") (pintype "passive"))
    )
    (net (code "136") (name "/_M31A") (class "Default")
      (node (ref "IC16") (pin "2") (pinfunction "A1_2") (pintype "input"))
      (node (ref "JP2") (pin "4") (pinfunction "4_4") (pintype "passive"))
    )
    (net (code "137") (name "/_M31B") (class "Default")
      (node (ref "IC16") (pin "4") (pinfunction "A2_4") (pintype "input"))
      (node (ref "JP2") (pin "6") (pinfunction "6_6") (pintype "passive"))
    )
    (net (code "138") (name "/_M32A") (class "Default")
      (node (ref "IC16") (pin "6") (pinfunction "A3_6") (pintype "input"))
      (node (ref "JP2") (pin "8") (pinfunction "8_8") (pintype "passive"))
    )
    (net (code "139") (name "/_M32B") (class "Default")
      (node (ref "IC16") (pin "10") (pinfunction "A4_10") (pintype "input"))
      (node (ref "JP2") (pin "10") (pinfunction "10_10") (pintype "passive"))
    )
    (net (code "140") (name "/_M33A") (class "Default")
      (node (ref "IC16") (pin "12") (pinfunction "A5_12") (pintype "input"))
      (node (ref "JP2") (pin "12") (pinfunction "12_12") (pintype "passive"))
    )
    (net (code "141") (name "/_M33B") (class "Default")
      (node (ref "IC16") (pin "14") (pinfunction "A6_14") (pintype "input"))
      (node (ref "JP2") (pin "14") (pinfunction "14_14") (pintype "passive"))
    )
    (net (code "142") (name "/_M41A") (class "Default")
      (node (ref "IC18") (pin "2") (pinfunction "A1_2") (pintype "input"))
      (node (ref "JP2") (pin "28") (pinfunction "28_28") (pintype "passive"))
    )
    (net (code "143") (name "/_M41B") (class "Default")
      (node (ref "IC18") (pin "4") (pinfunction "A2_4") (pintype "input"))
      (node (ref "JP2") (pin "30") (pinfunction "30_30") (pintype "passive"))
    )
    (net (code "144") (name "/_M42A") (class "Default")
      (node (ref "IC18") (pin "6") (pinfunction "A3_6") (pintype "input"))
      (node (ref "JP2") (pin "32") (pinfunction "32_32") (pintype "passive"))
    )
    (net (code "145") (name "/_M42B") (class "Default")
      (node (ref "IC18") (pin "10") (pinfunction "A4_10") (pintype "input"))
      (node (ref "JP2") (pin "34") (pinfunction "34_34") (pintype "passive"))
    )
    (net (code "146") (name "/_M43A") (class "Default")
      (node (ref "IC18") (pin "12") (pinfunction "A5_12") (pintype "input"))
      (node (ref "JP2") (pin "36") (pinfunction "36_36") (pintype "passive"))
    )
    (net (code "147") (name "/_M43B") (class "Default")
      (node (ref "IC18") (pin "14") (pinfunction "A6_14") (pintype "input"))
      (node (ref "JP2") (pin "38") (pinfunction "38_38") (pintype "passive"))
    )
    (net (code "148") (name "/_MD1A") (class "Default")
      (node (ref "IC23") (pin "2") (pinfunction "A1_2") (pintype "input"))
      (node (ref "JP1") (pin "15") (pinfunction "15_15") (pintype "passive"))
    )
    (net (code "149") (name "/_MD1B") (class "Default")
      (node (ref "IC23") (pin "4") (pinfunction "A2_4") (pintype "input"))
      (node (ref "JP1") (pin "17") (pinfunction "17_17") (pintype "passive"))
    )
    (net (code "150") (name "/_MD2A") (class "Default")
      (node (ref "IC23") (pin "6") (pinfunction "A3_6") (pintype "input"))
      (node (ref "JP2") (pin "13") (pinfunction "13_13") (pintype "passive"))
    )
    (net (code "151") (name "/_MD2B") (class "Default")
      (node (ref "IC23") (pin "10") (pinfunction "A4_10") (pintype "input"))
      (node (ref "JP1") (pin "21") (pinfunction "21_21") (pintype "passive"))
    )
    (net (code "152") (name "/_MD3A") (class "Default")
      (node (ref "IC23") (pin "12") (pinfunction "A5_12") (pintype "input"))
      (node (ref "JP1") (pin "23") (pinfunction "23_23") (pintype "passive"))
    )
    (net (code "153") (name "/_MD3B") (class "Default")
      (node (ref "IC23") (pin "14") (pinfunction "A6_14") (pintype "input"))
      (node (ref "JP1") (pin "25") (pinfunction "25_25") (pintype "passive"))
    )
    (net (code "154") (name "/_MDH1") (class "Default")
      (node (ref "IC24") (pin "3") (pinfunction "Y1_3") (pintype "tri_state"))
      (node (ref "JP1") (pin "16") (pinfunction "16_16") (pintype "passive"))
    )
    (net (code "155") (name "/_MDH2") (class "Default")
      (node (ref "IC24") (pin "5") (pinfunction "Y2_5") (pintype "tri_state"))
      (node (ref "JP1") (pin "18") (pinfunction "18_18") (pintype "passive"))
    )
    (net (code "156") (name "/_MDH3") (class "Default")
      (node (ref "IC24") (pin "7") (pinfunction "Y3_7") (pintype "tri_state"))
      (node (ref "JP2") (pin "17") (pinfunction "17_17") (pintype "passive"))
    )
    (net (code "157") (name "GND") (class "Default")
      (node (ref "C1") (pin "2") (pinfunction "2_2") (pintype "passive"))
      (node (ref "C10") (pin "2") (pinfunction "2_2") (pintype "passive"))
      (node (ref "C2") (pin "1") (pinfunction "1_1") (pintype "passive"))
      (node (ref "C3") (pin "2") (pinfunction "2_2") (pintype "passive"))
      (node (ref "C4") (pin "2") (pinfunction "2_2") (pintype "passive"))
      (node (ref "C5") (pin "2") (pinfunction "2_2") (pintype "passive"))
      (node (ref "C6") (pin "1") (pinfunction "1_1") (pintype "passive"))
      (node (ref "C7") (pin "1") (pinfunction "1_1") (pintype "passive"))
      (node (ref "C8") (pin "1") (pinfunction "1_1") (pintype "passive"))
      (node (ref "C9") (pin "2") (pinfunction "2_2") (pintype "passive"))
      (node (ref "IC1") (pin "2") (pinfunction "GND_2") (pintype "passive"))
      (node (ref "IC2") (pin "2") (pinfunction "GND_2") (pintype "passive"))
      (node (ref "IC3") (pin "2") (pinfunction "GND_2") (pintype "passive"))
      (node (ref "J1") (pin "3") (pinfunction "3_3") (pintype "passive"))
      (node (ref "J2") (pin "3") (pinfunction "3_3") (pintype "passive"))
      (node (ref "J3") (pin "3") (pinfunction "3_3") (pintype "passive"))
      (node (ref "J4") (pin "3") (pinfunction "3_3") (pintype "passive"))
      (node (ref "J5") (pin "GND") (pinfunction "-_GND") (pintype "passive"))
      (node (ref "J6") (pin "4") (pinfunction "4_4") (pintype "bidirectional"))
      (node (ref "J7") (pin "4") (pinfunction "4_4") (pintype "bidirectional"))
      (node (ref "J8") (pin "4") (pinfunction "4_4") (pintype "bidirectional"))
      (node (ref "J9") (pin "4") (pinfunction "4_4") (pintype "bidirectional"))
      (node (ref "JP1") (pin "1") (pinfunction "1_1") (pintype "passive"))
      (node (ref "JP1") (pin "19") (pinfunction "19_19") (pintype "passive"))
      (node (ref "JP1") (pin "20") (pinfunction "20_20") (pintype "passive"))
      (node (ref "JP1") (pin "39") (pinfunction "39_39") (pintype "passive"))
      (node (ref "JP2") (pin "2") (pinfunction "2_2") (pintype "passive"))
      (node (ref "JP2") (pin "40") (pinfunction "40_40") (pintype "passive"))
      (node (ref "JP5") (pin "3") (pinfunction "3_3") (pintype "passive"))
      (node (ref "JP5") (pin "4") (pinfunction "4_4") (pintype "passive"))
      (node (ref "JP6") (pin "3") (pinfunction "3_3") (pintype "passive"))
      (node (ref "JP6") (pin "4") (pinfunction "4_4") (pintype "passive"))
      (node (ref "LED1") (pin "C") (pinfunction "C_C") (pintype "passive"))
      (node (ref "LED2") (pin "C") (pinfunction "C_C") (pintype "passive"))
      (node (ref "LED3") (pin "C") (pinfunction "C_C") (pintype "passive"))
      (node (ref "LED4") (pin "C") (pinfunction "C_C") (pintype "passive"))
      (node (ref "LED5") (pin "C") (pinfunction "C_C") (pintype "passive"))
      (node (ref "LED6") (pin "C") (pinfunction "C_C") (pintype "passive"))
      (node (ref "LED7") (pin "C") (pinfunction "C_C") (pintype "passive"))
      (node (ref "S1") (pin "2") (pinfunction "P_2") (pintype "passive"))
      (node (ref "S1") (pin "4") (pinfunction "P_4") (pintype "passive"))
      (node (ref "S2") (pin "2") (pinfunction "P_2") (pintype "passive"))
      (node (ref "S2") (pin "4") (pinfunction "P_4") (pintype "passive"))
      (node (ref "S3") (pin "2") (pinfunction "P_2") (pintype "passive"))
      (node (ref "S3") (pin "4") (pinfunction "P_4") (pintype "passive"))
      (node (ref "SV1") (pin "1") (pinfunction "1_1") (pintype "passive"))
      (node (ref "SV1") (pin "2") (pinfunction "2_2") (pintype "passive"))
      (node (ref "SV14") (pin "1") (pinfunction "1_1") (pintype "passive"))
      (node (ref "SV14") (pin "2") (pinfunction "2_2") (pintype "passive"))
      (node (ref "SV2") (pin "1") (pinfunction "1_1") (pintype "passive"))
      (node (ref "SV2") (pin "2") (pinfunction "2_2") (pintype "passive"))
      (node (ref "SV3") (pin "1") (pinfunction "1_1") (pintype "passive"))
      (node (ref "SV3") (pin "2") (pinfunction "2_2") (pintype "passive"))
      (node (ref "SV4") (pin "1") (pinfunction "1_1") (pintype "passive"))
      (node (ref "SV4") (pin "2") (pinfunction "2_2") (pintype "passive"))
      (node (ref "SV5") (pin "8") (pinfunction "8_8") (pintype "passive"))
      (node (ref "SV8") (pin "4") (pinfunction "4_4") (pintype "passive"))
      (node (ref "U$4") (pin "GND") (pinfunction "GND_GND") (pintype "bidirectional"))
      (node (ref "U$4") (pin "GNDO") (pinfunction "GNDO_GNDO") (pintype "bidirectional"))
      (node (ref "X1") (pin "1") (pinfunction "S_1") (pintype "passive"))
    )
    (net (code "158") (name "Net-(J5-+)") (class "Default")
      (node (ref "J5") (pin "BATT") (pinfunction "+_BATT") (pintype "passive"))
      (node (ref "U$5") (pin "P$2") (pinfunction "P_P$2") (pintype "passive"))
    )
    (net (code "159") (name "Net-(JP5-Pad1)") (class "Default")
      (node (ref "JP5") (pin "1") (pinfunction "1_1") (pintype "passive"))
      (node (ref "JP5") (pin "2") (pinfunction "2_2") (pintype "passive"))
    )
    (net (code "160") (name "Net-(JP5-Pad5)") (class "Default")
      (node (ref "JP5") (pin "5") (pinfunction "5_5") (pintype "passive"))
      (node (ref "JP5") (pin "6") (pinfunction "6_6") (pintype "passive"))
    )
    (net (code "161") (name "Net-(JP5-Pad7)") (class "Default")
      (node (ref "JP5") (pin "7") (pinfunction "7_7") (pintype "passive"))
      (node (ref "JP5") (pin "8") (pinfunction "8_8") (pintype "passive"))
    )
    (net (code "162") (name "Net-(JP5-Pad10)") (class "Default")
      (node (ref "JP5") (pin "10") (pinfunction "10_10") (pintype "passive"))
      (node (ref "JP5") (pin "9") (pinfunction "9_9") (pintype "passive"))
    )
    (net (code "163") (name "Net-(JP5-Pad11)") (class "Default")
      (node (ref "JP5") (pin "11") (pinfunction "11_11") (pintype "passive"))
      (node (ref "JP5") (pin "12") (pinfunction "12_12") (pintype "passive"))
    )
    (net (code "164") (name "Net-(JP5-Pad13)") (class "Default")
      (node (ref "JP5") (pin "13") (pinfunction "13_13") (pintype "passive"))
      (node (ref "JP5") (pin "14") (pinfunction "14_14") (pintype "passive"))
    )
    (net (code "165") (name "Net-(JP5-Pad15)") (class "Default")
      (node (ref "JP5") (pin "15") (pinfunction "15_15") (pintype "passive"))
      (node (ref "JP5") (pin "16") (pinfunction "16_16") (pintype "passive"))
    )
    (net (code "166") (name "Net-(JP5-Pad17)") (class "Default")
      (node (ref "JP5") (pin "17") (pinfunction "17_17") (pintype "passive"))
      (node (ref "JP5") (pin "18") (pinfunction "18_18") (pintype "passive"))
    )
    (net (code "167") (name "Net-(JP5-Pad19)") (class "Default")
      (node (ref "JP5") (pin "19") (pinfunction "19_19") (pintype "passive"))
      (node (ref "JP5") (pin "20") (pinfunction "20_20") (pintype "passive"))
    )
    (net (code "168") (name "Net-(JP5-Pad21)") (class "Default")
      (node (ref "JP5") (pin "21") (pinfunction "21_21") (pintype "passive"))
      (node (ref "JP5") (pin "22") (pinfunction "22_22") (pintype "passive"))
    )
    (net (code "169") (name "Net-(JP5-Pad27)") (class "Default")
      (node (ref "JP5") (pin "27") (pinfunction "27_27") (pintype "passive"))
      (node (ref "JP5") (pin "28") (pinfunction "28_28") (pintype "passive"))
    )
    (net (code "170") (name "Net-(JP5-Pad29)") (class "Default")
      (node (ref "JP5") (pin "29") (pinfunction "29_29") (pintype "passive"))
      (node (ref "JP5") (pin "30") (pinfunction "30_30") (pintype "passive"))
    )
    (net (code "171") (name "Net-(JP6-Pad5)") (class "Default")
      (node (ref "JP6") (pin "5") (pinfunction "5_5") (pintype "passive"))
      (node (ref "JP6") (pin "6") (pinfunction "6_6") (pintype "passive"))
    )
    (net (code "172") (name "Net-(JP6-Pad7)") (class "Default")
      (node (ref "JP6") (pin "7") (pinfunction "7_7") (pintype "passive"))
      (node (ref "JP6") (pin "8") (pinfunction "8_8") (pintype "passive"))
    )
    (net (code "173") (name "Net-(JP6-Pad10)") (class "Default")
      (node (ref "JP6") (pin "10") (pinfunction "10_10") (pintype "passive"))
      (node (ref "JP6") (pin "9") (pinfunction "9_9") (pintype "passive"))
    )
    (net (code "174") (name "Net-(JP6-Pad11)") (class "Default")
      (node (ref "JP6") (pin "11") (pinfunction "11_11") (pintype "passive"))
      (node (ref "JP6") (pin "12") (pinfunction "12_12") (pintype "passive"))
    )
    (net (code "175") (name "Net-(JP6-Pad25)") (class "Default")
      (node (ref "JP6") (pin "25") (pinfunction "25_25") (pintype "passive"))
      (node (ref "JP6") (pin "26") (pinfunction "26_26") (pintype "passive"))
    )
    (net (code "176") (name "Net-(JP6-Pad27)") (class "Default")
      (node (ref "JP6") (pin "27") (pinfunction "27_27") (pintype "passive"))
      (node (ref "JP6") (pin "28") (pinfunction "28_28") (pintype "passive"))
    )
    (net (code "177") (name "Net-(JP6-Pad29)") (class "Default")
      (node (ref "JP6") (pin "29") (pinfunction "29_29") (pintype "passive"))
      (node (ref "JP6") (pin "30") (pinfunction "30_30") (pintype "passive"))
    )
    (net (code "178") (name "Net-(LED1-PadA)") (class "Default")
      (node (ref "LED1") (pin "A") (pinfunction "A_A") (pintype "passive"))
      (node (ref "R1") (pin "2") (pinfunction "2_2") (pintype "passive"))
    )
    (net (code "179") (name "Net-(LED2-PadA)") (class "Default")
      (node (ref "LED2") (pin "A") (pinfunction "A_A") (pintype "passive"))
      (node (ref "R2") (pin "2") (pinfunction "2_2") (pintype "passive"))
    )
    (net (code "180") (name "Net-(LED3-PadA)") (class "Default")
      (node (ref "LED3") (pin "A") (pinfunction "A_A") (pintype "passive"))
      (node (ref "R3") (pin "2") (pinfunction "2_2") (pintype "passive"))
    )
    (net (code "181") (name "Net-(LED4-PadA)") (class "Default")
      (node (ref "LED4") (pin "A") (pinfunction "A_A") (pintype "passive"))
      (node (ref "R4") (pin "2") (pinfunction "2_2") (pintype "passive"))
    )
    (net (code "182") (name "Net-(LED5-PadA)") (class "Default")
      (node (ref "LED5") (pin "A") (pinfunction "A_A") (pintype "passive"))
      (node (ref "R5") (pin "2") (pinfunction "2_2") (pintype "passive"))
    )
    (net (code "183") (name "Net-(LED6-PadA)") (class "Default")
      (node (ref "LED6") (pin "A") (pinfunction "A_A") (pintype "passive"))
      (node (ref "R6") (pin "2") (pinfunction "2_2") (pintype "passive"))
    )
    (net (code "184") (name "Net-(LED7-PadA)") (class "Default")
      (node (ref "LED7") (pin "A") (pinfunction "A_A") (pintype "passive"))
      (node (ref "R7") (pin "2") (pinfunction "2_2") (pintype "passive"))
    )
    (net (code "185") (name "Net-(U$5-S)") (class "Default")
      (node (ref "U$5") (pin "P$1") (pinfunction "S_P$1") (pintype "passive"))
      (node (ref "U1") (pin "1") (pinfunction "~{A}_1") (pintype "bidirectional"))
      (node (ref "U1") (pin "3") (pinfunction "A_3") (pintype "bidirectional"))
      (node (ref "U2") (pin "1") (pinfunction "~{A}_1") (pintype "bidirectional"))
      (node (ref "U2") (pin "3") (pinfunction "A_3") (pintype "bidirectional"))
      (node (ref "U3") (pin "1") (pinfunction "~{A}_1") (pintype "bidirectional"))
      (node (ref "U3") (pin "3") (pinfunction "A_3") (pintype "bidirectional"))
    )
    (net (code "186") (name "unconnected-(IC19A-A3-Pad6)") (class "Default")
      (node (ref "IC19") (pin "6") (pinfunction "A3_6") (pintype "input"))
    )
    (net (code "187") (name "unconnected-(IC19A-Y3-Pad7)") (class "Default")
      (node (ref "IC19") (pin "7") (pinfunction "Y3_7") (pintype "tri_state"))
    )
    (net (code "188") (name "unconnected-(IC20A-A6-Pad14)") (class "Default")
      (node (ref "IC20") (pin "14") (pinfunction "A6_14") (pintype "input"))
    )
    (net (code "189") (name "unconnected-(IC20A-Y6-Pad13)") (class "Default")
      (node (ref "IC20") (pin "13") (pinfunction "Y6_13") (pintype "tri_state"))
    )
    (net (code "190") (name "unconnected-(IC21A-A6-Pad14)") (class "Default")
      (node (ref "IC21") (pin "14") (pinfunction "A6_14") (pintype "input"))
    )
    (net (code "191") (name "unconnected-(IC21A-Y6-Pad13)") (class "Default")
      (node (ref "IC21") (pin "13") (pinfunction "Y6_13") (pintype "tri_state"))
    )
    (net (code "192") (name "unconnected-(IC22A-A6-Pad14)") (class "Default")
      (node (ref "IC22") (pin "14") (pinfunction "A6_14") (pintype "input"))
    )
    (net (code "193") (name "unconnected-(IC22A-Y6-Pad13)") (class "Default")
      (node (ref "IC22") (pin "13") (pinfunction "Y6_13") (pintype "tri_state"))
    )
    (net (code "194") (name "unconnected-(IC25A-A6-Pad14)") (class "Default")
      (node (ref "IC25") (pin "14") (pinfunction "A6_14") (pintype "input"))
    )
    (net (code "195") (name "unconnected-(IC25A-Y6-Pad13)") (class "Default")
      (node (ref "IC25") (pin "13") (pinfunction "Y6_13") (pintype "tri_state"))
    )
    (net (code "196") (name "unconnected-(IC26A-A4-Pad10)") (class "Default")
      (node (ref "IC26") (pin "10") (pinfunction "A4_10") (pintype "input"))
    )
    (net (code "197") (name "unconnected-(IC26A-A5-Pad12)") (class "Default")
      (node (ref "IC26") (pin "12") (pinfunction "A5_12") (pintype "input"))
    )
    (net (code "198") (name "unconnected-(IC26A-A6-Pad14)") (class "Default")
      (node (ref "IC26") (pin "14") (pinfunction "A6_14") (pintype "input"))
    )
    (net (code "199") (name "unconnected-(IC26A-Y4-Pad9)") (class "Default")
      (node (ref "IC26") (pin "9") (pinfunction "Y4_9") (pintype "tri_state"))
    )
    (net (code "200") (name "unconnected-(IC26A-Y5-Pad11)") (class "Default")
      (node (ref "IC26") (pin "11") (pinfunction "Y5_11") (pintype "tri_state"))
    )
    (net (code "201") (name "unconnected-(IC26A-Y6-Pad13)") (class "Default")
      (node (ref "IC26") (pin "13") (pinfunction "Y6_13") (pintype "tri_state"))
    )
    (net (code "202") (name "unconnected-(J1-Pad1)") (class "Default")
      (node (ref "J1") (pin "1") (pinfunction "1_1") (pintype "passive"))
    )
    (net (code "203") (name "unconnected-(J1-Pad4)") (class "Default")
      (node (ref "J1") (pin "4") (pinfunction "4_4") (pintype "passive"))
    )
    (net (code "204") (name "unconnected-(J1-Pad5)") (class "Default")
      (node (ref "J1") (pin "5") (pinfunction "5_5") (pintype "passive"))
    )
    (net (code "205") (name "unconnected-(J1-Pad7)") (class "Default")
      (node (ref "J1") (pin "7") (pinfunction "7_7") (pintype "passive"))
    )
    (net (code "206") (name "unconnected-(J1-Pad9)") (class "Default")
      (node (ref "J1") (pin "9") (pinfunction "9_9") (pintype "passive"))
    )
    (net (code "207") (name "unconnected-(J1-Pad10)") (class "Default")
      (node (ref "J1") (pin "10") (pinfunction "10_10") (pintype "passive"))
    )
    (net (code "208") (name "unconnected-(J2-Pad1)") (class "Default")
      (node (ref "J2") (pin "1") (pinfunction "1_1") (pintype "passive"))
    )
    (net (code "209") (name "unconnected-(J2-Pad4)") (class "Default")
      (node (ref "J2") (pin "4") (pinfunction "4_4") (pintype "passive"))
    )
    (net (code "210") (name "unconnected-(J2-Pad5)") (class "Default")
      (node (ref "J2") (pin "5") (pinfunction "5_5") (pintype "passive"))
    )
    (net (code "211") (name "unconnected-(J2-Pad7)") (class "Default")
      (node (ref "J2") (pin "7") (pinfunction "7_7") (pintype "passive"))
    )
    (net (code "212") (name "unconnected-(J2-Pad9)") (class "Default")
      (node (ref "J2") (pin "9") (pinfunction "9_9") (pintype "passive"))
    )
    (net (code "213") (name "unconnected-(J2-Pad10)") (class "Default")
      (node (ref "J2") (pin "10") (pinfunction "10_10") (pintype "passive"))
    )
    (net (code "214") (name "unconnected-(J3-Pad1)") (class "Default")
      (node (ref "J3") (pin "1") (pinfunction "1_1") (pintype "passive"))
    )
    (net (code "215") (name "unconnected-(J3-Pad4)") (class "Default")
      (node (ref "J3") (pin "4") (pinfunction "4_4") (pintype "passive"))
    )
    (net (code "216") (name "unconnected-(J3-Pad5)") (class "Default")
      (node (ref "J3") (pin "5") (pinfunction "5_5") (pintype "passive"))
    )
    (net (code "217") (name "unconnected-(J3-Pad7)") (class "Default")
      (node (ref "J3") (pin "7") (pinfunction "7_7") (pintype "passive"))
    )
    (net (code "218") (name "unconnected-(J3-Pad9)") (class "Default")
      (node (ref "J3") (pin "9") (pinfunction "9_9") (pintype "passive"))
    )
    (net (code "219") (name "unconnected-(J3-Pad10)") (class "Default")
      (node (ref "J3") (pin "10") (pinfunction "10_10") (pintype "passive"))
    )
    (net (code "220") (name "unconnected-(J4-Pad1)") (class "Default")
      (node (ref "J4") (pin "1") (pinfunction "1_1") (pintype "passive"))
    )
    (net (code "221") (name "unconnected-(J4-Pad4)") (class "Default")
      (node (ref "J4") (pin "4") (pinfunction "4_4") (pintype "passive"))
    )
    (net (code "222") (name "unconnected-(J4-Pad5)") (class "Default")
      (node (ref "J4") (pin "5") (pinfunction "5_5") (pintype "passive"))
    )
    (net (code "223") (name "unconnected-(J4-Pad7)") (class "Default")
      (node (ref "J4") (pin "7") (pinfunction "7_7") (pintype "passive"))
    )
    (net (code "224") (name "unconnected-(J4-Pad9)") (class "Default")
      (node (ref "J4") (pin "9") (pinfunction "9_9") (pintype "passive"))
    )
    (net (code "225") (name "unconnected-(J4-Pad10)") (class "Default")
      (node (ref "J4") (pin "10") (pinfunction "10_10") (pintype "passive"))
    )
    (net (code "226") (name "unconnected-(J6-Pad6)") (class "Default")
      (node (ref "J6") (pin "6") (pinfunction "6_6") (pintype "bidirectional"))
    )
    (net (code "227") (name "unconnected-(J7-Pad6)") (class "Default")
      (node (ref "J7") (pin "6") (pinfunction "6_6") (pintype "bidirectional"))
    )
    (net (code "228") (name "unconnected-(J8-Pad6)") (class "Default")
      (node (ref "J8") (pin "6") (pinfunction "6_6") (pintype "bidirectional"))
    )
    (net (code "229") (name "unconnected-(J9-Pad6)") (class "Default")
      (node (ref "J9") (pin "6") (pinfunction "6_6") (pintype "bidirectional"))
    )
    (net (code "230") (name "unconnected-(JP1-Pad2)") (class "Default")
      (node (ref "JP1") (pin "2") (pinfunction "2_2") (pintype "passive"))
    )
    (net (code "231") (name "unconnected-(JP1-Pad14)") (class "Default")
      (node (ref "JP1") (pin "14") (pinfunction "14_14") (pintype "passive"))
    )
    (net (code "232") (name "unconnected-(JP1-Pad24)") (class "Default")
      (node (ref "JP1") (pin "24") (pinfunction "24_24") (pintype "passive"))
    )
    (net (code "233") (name "unconnected-(JP1-Pad26)") (class "Default")
      (node (ref "JP1") (pin "26") (pinfunction "26_26") (pintype "passive"))
    )
    (net (code "234") (name "unconnected-(JP1-Pad28)") (class "Default")
      (node (ref "JP1") (pin "28") (pinfunction "28_28") (pintype "passive"))
    )
    (net (code "235") (name "unconnected-(JP1-Pad40)") (class "Default")
      (node (ref "JP1") (pin "40") (pinfunction "40_40") (pintype "passive"))
    )
    (net (code "236") (name "unconnected-(JP2-Pad1)") (class "Default")
      (node (ref "JP2") (pin "1") (pinfunction "1_1") (pintype "passive"))
    )
    (net (code "237") (name "unconnected-(JP2-Pad19)") (class "Default")
      (node (ref "JP2") (pin "19") (pinfunction "19_19") (pintype "passive"))
    )
    (net (code "238") (name "unconnected-(JP2-Pad27)") (class "Default")
      (node (ref "JP2") (pin "27") (pinfunction "27_27") (pintype "passive"))
    )
    (net (code "239") (name "unconnected-(JP2-Pad39)") (class "Default")
      (node (ref "JP2") (pin "39") (pinfunction "39_39") (pintype "passive"))
    )
    (net (code "240") (name "unconnected-(X2D-S-Pad4)") (class "Default")
      (node (ref "X2") (pin "4") (pinfunction "S_4") (pintype "passive"))
    )
    (net (code "241") (name "unconnected-(X3D-S-Pad4)") (class "Default")
      (node (ref "X3") (pin "4") (pinfunction "S_4") (pintype "passive"))
    )
    (net (code "242") (name "unconnected-(X4D-S-Pad4)") (class "Default")
      (node (ref "X4") (pin "4") (pinfunction "S_4") (pintype "passive"))
    )
    (net (code "243") (name "unconnected-(X5D-S-Pad4)") (class "Default")
      (node (ref "X5") (pin "4") (pinfunction "S_4") (pintype "passive"))
    )
  )
)
